# buttons.net
KiCad netlist of a schematic drawn in EAGLE
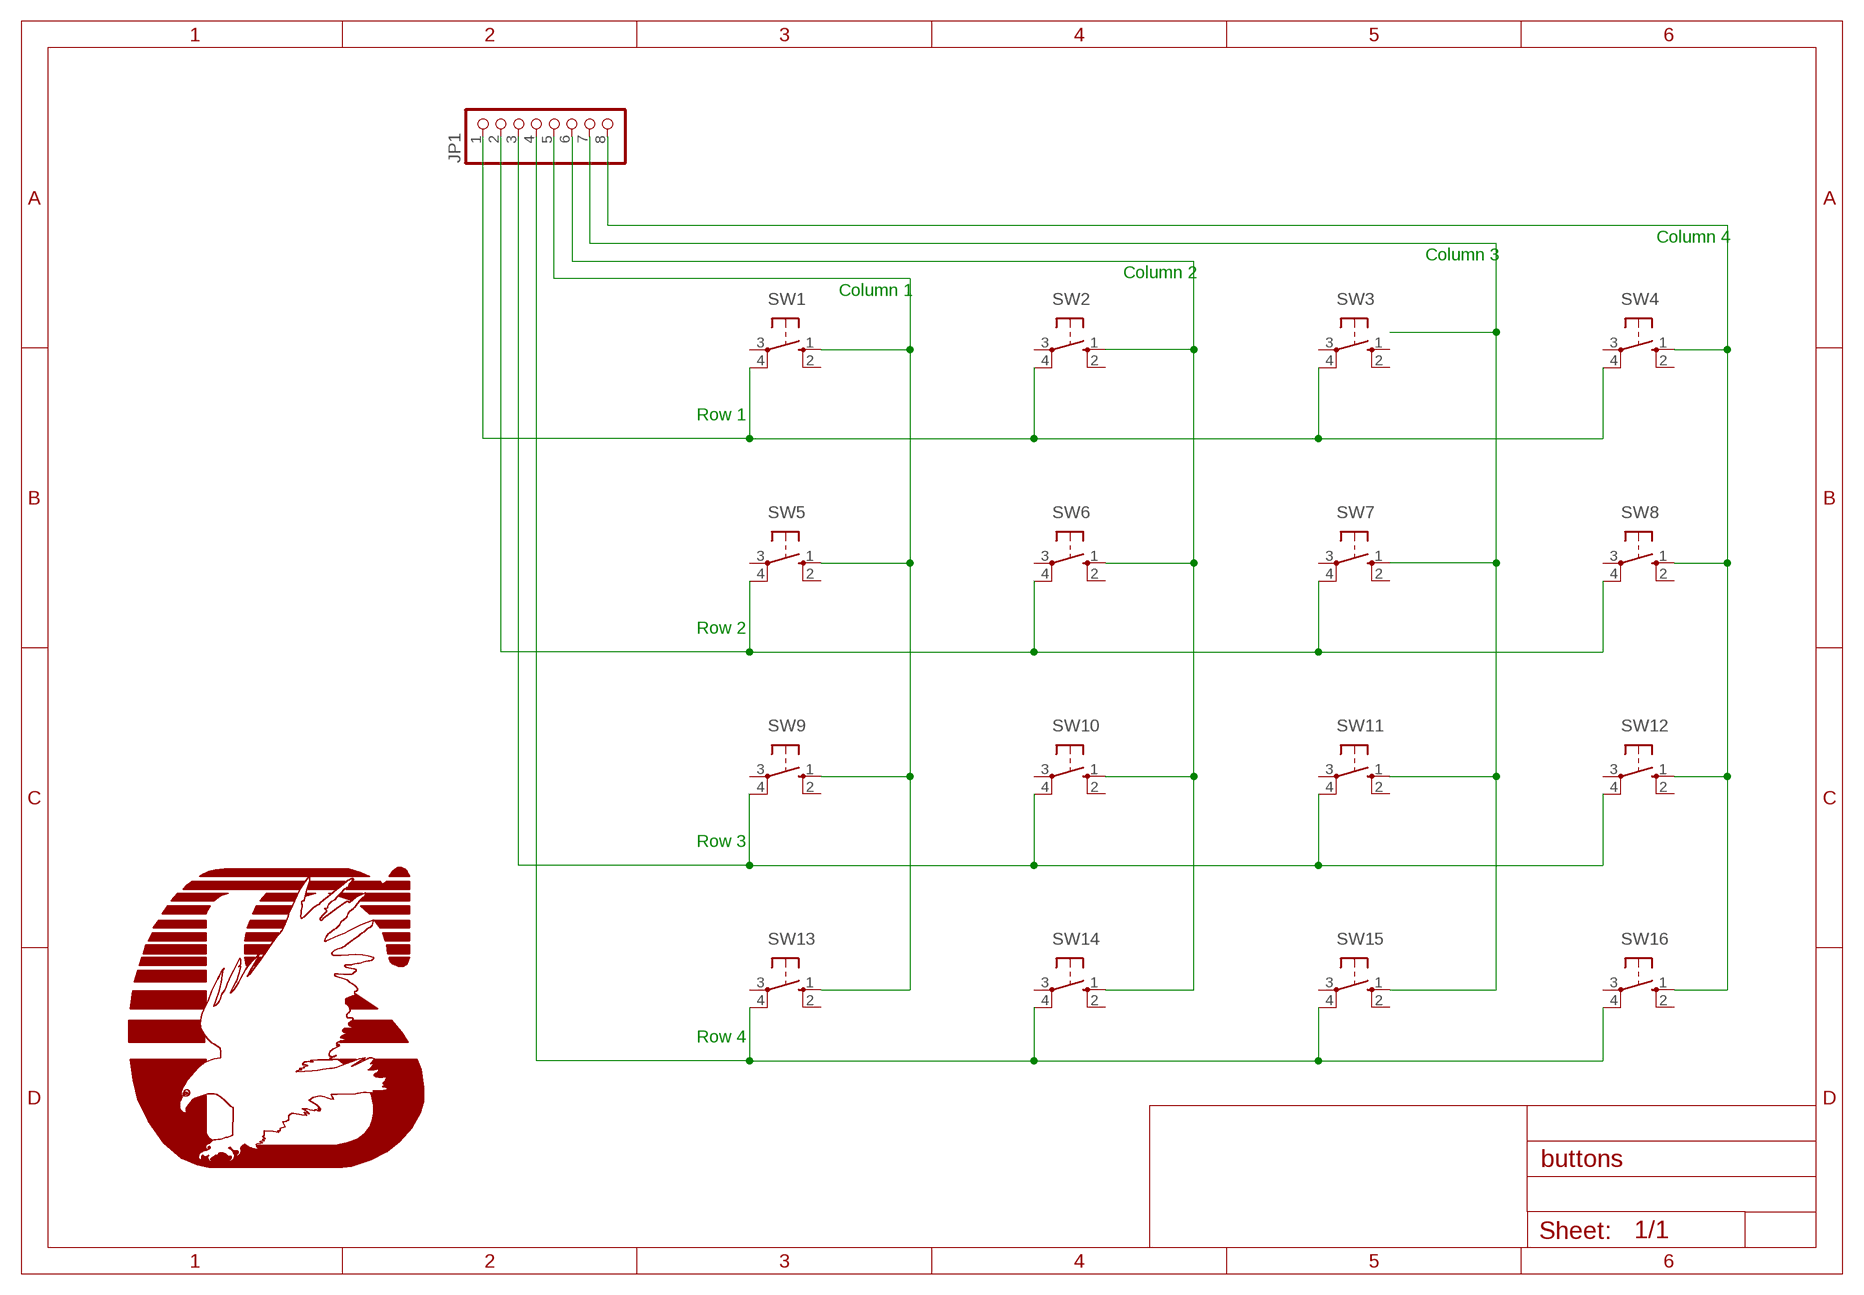
[diagram p0: schematic, sheet 1]

(export (version "E")
  (design (tool "Eeschema 10.0.6"))
  (components
    (comp (ref "JP1")
      (value "PINHD-1X8-3.5MM")
      (footprint "eagle-import:1X08-3.5MM")
      (libsource (lib "eagle-import") (part "PINHD-1X8-3.5MM"))
    )
    (comp (ref "SW1")
      (value "10-XX")
      (footprint "eagle-import:B3F-10XX")
      (libsource (lib "eagle-import") (part "10-XX"))
    )
    (comp (ref "SW2")
      (value "10-XX")
      (footprint "eagle-import:B3F-10XX")
      (libsource (lib "eagle-import") (part "10-XX"))
    )
    (comp (ref "SW3")
      (value "10-XX")
      (footprint "eagle-import:B3F-10XX")
      (libsource (lib "eagle-import") (part "10-XX"))
    )
    (comp (ref "SW4")
      (value "10-XX")
      (footprint "eagle-import:B3F-10XX")
      (libsource (lib "eagle-import") (part "10-XX"))
    )
    (comp (ref "SW5")
      (value "10-XX")
      (footprint "eagle-import:B3F-10XX")
      (libsource (lib "eagle-import") (part "10-XX"))
    )
    (comp (ref "SW6")
      (value "10-XX")
      (footprint "eagle-import:B3F-10XX")
      (libsource (lib "eagle-import") (part "10-XX"))
    )
    (comp (ref "SW7")
      (value "10-XX")
      (footprint "eagle-import:B3F-10XX")
      (libsource (lib "eagle-import") (part "10-XX"))
    )
    (comp (ref "SW8")
      (value "10-XX")
      (footprint "eagle-import:B3F-10XX")
      (libsource (lib "eagle-import") (part "10-XX"))
    )
    (comp (ref "SW9")
      (value "10-XX")
      (footprint "eagle-import:B3F-10XX")
      (libsource (lib "eagle-import") (part "10-XX"))
    )
    (comp (ref "SW10")
      (value "10-XX")
      (footprint "eagle-import:B3F-10XX")
      (libsource (lib "eagle-import") (part "10-XX"))
    )
    (comp (ref "SW11")
      (value "10-XX")
      (footprint "eagle-import:B3F-10XX")
      (libsource (lib "eagle-import") (part "10-XX"))
    )
    (comp (ref "SW12")
      (value "10-XX")
      (footprint "eagle-import:B3F-10XX")
      (libsource (lib "eagle-import") (part "10-XX"))
    )
    (comp (ref "SW13")
      (value "10-XX")
      (footprint "eagle-import:B3F-10XX")
      (libsource (lib "eagle-import") (part "10-XX"))
    )
    (comp (ref "SW14")
      (value "10-XX")
      (footprint "eagle-import:B3F-10XX")
      (libsource (lib "eagle-import") (part "10-XX"))
    )
    (comp (ref "SW15")
      (value "10-XX")
      (footprint "eagle-import:B3F-10XX")
      (libsource (lib "eagle-import") (part "10-XX"))
    )
    (comp (ref "SW16")
      (value "10-XX")
      (footprint "eagle-import:B3F-10XX")
      (libsource (lib "eagle-import") (part "10-XX"))
    )
  )
  (nets
    (net (code "1") (name "Net-(SW1-P1)") (class "Default")
      (node (ref "JP1") (pin "1") (pinfunction "1_1") (pintype "passive"))
      (node (ref "SW1") (pin "4") (pinfunction "P1_4") (pintype "passive"))
      (node (ref "SW2") (pin "4") (pinfunction "P1_4") (pintype "passive"))
      (node (ref "SW3") (pin "4") (pinfunction "P1_4") (pintype "passive"))
      (node (ref "SW4") (pin "4") (pinfunction "P1_4") (pintype "passive"))
    )
    (net (code "2") (name "Net-(SW1-S)") (class "Default")
      (node (ref "JP1") (pin "5") (pinfunction "5_5") (pintype "passive"))
      (node (ref "SW1") (pin "1") (pinfunction "S_1") (pintype "passive"))
      (node (ref "SW13") (pin "1") (pinfunction "S_1") (pintype "passive"))
      (node (ref "SW5") (pin "1") (pinfunction "S_1") (pintype "passive"))
      (node (ref "SW9") (pin "1") (pinfunction "S_1") (pintype "passive"))
    )
    (net (code "3") (name "Net-(SW5-P1)") (class "Default")
      (node (ref "JP1") (pin "2") (pinfunction "2_2") (pintype "passive"))
      (node (ref "SW5") (pin "4") (pinfunction "P1_4") (pintype "passive"))
      (node (ref "SW6") (pin "4") (pinfunction "P1_4") (pintype "passive"))
      (node (ref "SW7") (pin "4") (pinfunction "P1_4") (pintype "passive"))
      (node (ref "SW8") (pin "4") (pinfunction "P1_4") (pintype "passive"))
    )
    (net (code "4") (name "Net-(SW10-P1)") (class "Default")
      (node (ref "JP1") (pin "3") (pinfunction "3_3") (pintype "passive"))
      (node (ref "SW10") (pin "4") (pinfunction "P1_4") (pintype "passive"))
      (node (ref "SW11") (pin "4") (pinfunction "P1_4") (pintype "passive"))
      (node (ref "SW12") (pin "4") (pinfunction "P1_4") (pintype "passive"))
      (node (ref "SW9") (pin "4") (pinfunction "P1_4") (pintype "passive"))
    )
    (net (code "5") (name "Net-(SW10-S)") (class "Default")
      (node (ref "JP1") (pin "6") (pinfunction "6_6") (pintype "passive"))
      (node (ref "SW10") (pin "1") (pinfunction "S_1") (pintype "passive"))
      (node (ref "SW14") (pin "1") (pinfunction "S_1") (pintype "passive"))
      (node (ref "SW2") (pin "1") (pinfunction "S_1") (pintype "passive"))
      (node (ref "SW6") (pin "1") (pinfunction "S_1") (pintype "passive"))
    )
    (net (code "6") (name "Net-(SW11-S)") (class "Default")
      (node (ref "JP1") (pin "7") (pinfunction "7_7") (pintype "passive"))
      (node (ref "SW11") (pin "1") (pinfunction "S_1") (pintype "passive"))
      (node (ref "SW15") (pin "1") (pinfunction "S_1") (pintype "passive"))
      (node (ref "SW7") (pin "1") (pinfunction "S_1") (pintype "passive"))
    )
    (net (code "7") (name "Net-(SW12-S)") (class "Default")
      (node (ref "JP1") (pin "8") (pinfunction "8_8") (pintype "passive"))
      (node (ref "SW12") (pin "1") (pinfunction "S_1") (pintype "passive"))
      (node (ref "SW16") (pin "1") (pinfunction "S_1") (pintype "passive"))
      (node (ref "SW4") (pin "1") (pinfunction "S_1") (pintype "passive"))
      (node (ref "SW8") (pin "1") (pinfunction "S_1") (pintype "passive"))
    )
    (net (code "8") (name "Net-(SW13-P1)") (class "Default")
      (node (ref "JP1") (pin "4") (pinfunction "4_4") (pintype "passive"))
      (node (ref "SW13") (pin "4") (pinfunction "P1_4") (pintype "passive"))
      (node (ref "SW14") (pin "4") (pinfunction "P1_4") (pintype "passive"))
      (node (ref "SW15") (pin "4") (pinfunction "P1_4") (pintype "passive"))
      (node (ref "SW16") (pin "4") (pinfunction "P1_4") (pintype "passive"))
    )
    (net (code "9") (name "unconnected-(SW1-P-Pad3)") (class "Default")
      (node (ref "SW1") (pin "3") (pinfunction "P_3") (pintype "passive"))
    )
    (net (code "10") (name "unconnected-(SW1-S1-Pad2)") (class "Default")
      (node (ref "SW1") (pin "2") (pinfunction "S1_2") (pintype "passive"))
    )
    (net (code "11") (name "unconnected-(SW2-P-Pad3)") (class "Default")
      (node (ref "SW2") (pin "3") (pinfunction "P_3") (pintype "passive"))
    )
    (net (code "12") (name "unconnected-(SW2-S1-Pad2)") (class "Default")
      (node (ref "SW2") (pin "2") (pinfunction "S1_2") (pintype "passive"))
    )
    (net (code "13") (name "unconnected-(SW3-P-Pad3)") (class "Default")
      (node (ref "SW3") (pin "3") (pinfunction "P_3") (pintype "passive"))
    )
    (net (code "14") (name "unconnected-(SW3-S-Pad1)") (class "Default")
      (node (ref "SW3") (pin "1") (pinfunction "S_1") (pintype "passive"))
    )
    (net (code "15") (name "unconnected-(SW3-S1-Pad2)") (class "Default")
      (node (ref "SW3") (pin "2") (pinfunction "S1_2") (pintype "passive"))
    )
    (net (code "16") (name "unconnected-(SW4-P-Pad3)") (class "Default")
      (node (ref "SW4") (pin "3") (pinfunction "P_3") (pintype "passive"))
    )
    (net (code "17") (name "unconnected-(SW4-S1-Pad2)") (class "Default")
      (node (ref "SW4") (pin "2") (pinfunction "S1_2") (pintype "passive"))
    )
    (net (code "18") (name "unconnected-(SW5-P-Pad3)") (class "Default")
      (node (ref "SW5") (pin "3") (pinfunction "P_3") (pintype "passive"))
    )
    (net (code "19") (name "unconnected-(SW5-S1-Pad2)") (class "Default")
      (node (ref "SW5") (pin "2") (pinfunction "S1_2") (pintype "passive"))
    )
    (net (code "20") (name "unconnected-(SW6-P-Pad3)") (class "Default")
      (node (ref "SW6") (pin "3") (pinfunction "P_3") (pintype "passive"))
    )
    (net (code "21") (name "unconnected-(SW6-S1-Pad2)") (class "Default")
      (node (ref "SW6") (pin "2") (pinfunction "S1_2") (pintype "passive"))
    )
    (net (code "22") (name "unconnected-(SW7-P-Pad3)") (class "Default")
      (node (ref "SW7") (pin "3") (pinfunction "P_3") (pintype "passive"))
    )
    (net (code "23") (name "unconnected-(SW7-S1-Pad2)") (class "Default")
      (node (ref "SW7") (pin "2") (pinfunction "S1_2") (pintype "passive"))
    )
    (net (code "24") (name "unconnected-(SW8-P-Pad3)") (class "Default")
      (node (ref "SW8") (pin "3") (pinfunction "P_3") (pintype "passive"))
    )
    (net (code "25") (name "unconnected-(SW8-S1-Pad2)") (class "Default")
      (node (ref "SW8") (pin "2") (pinfunction "S1_2") (pintype "passive"))
    )
    (net (code "26") (name "unconnected-(SW9-P-Pad3)") (class "Default")
      (node (ref "SW9") (pin "3") (pinfunction "P_3") (pintype "passive"))
    )
    (net (code "27") (name "unconnected-(SW9-S1-Pad2)") (class "Default")
      (node (ref "SW9") (pin "2") (pinfunction "S1_2") (pintype "passive"))
    )
    (net (code "28") (name "unconnected-(SW10-P-Pad3)") (class "Default")
      (node (ref "SW10") (pin "3") (pinfunction "P_3") (pintype "passive"))
    )
    (net (code "29") (name "unconnected-(SW10-S1-Pad2)") (class "Default")
      (node (ref "SW10") (pin "2") (pinfunction "S1_2") (pintype "passive"))
    )
    (net (code "30") (name "unconnected-(SW11-P-Pad3)") (class "Default")
      (node (ref "SW11") (pin "3") (pinfunction "P_3") (pintype "passive"))
    )
    (net (code "31") (name "unconnected-(SW11-S1-Pad2)") (class "Default")
      (node (ref "SW11") (pin "2") (pinfunction "S1_2") (pintype "passive"))
    )
    (net (code "32") (name "unconnected-(SW12-P-Pad3)") (class "Default")
      (node (ref "SW12") (pin "3") (pinfunction "P_3") (pintype "passive"))
    )
    (net (code "33") (name "unconnected-(SW12-S1-Pad2)") (class "Default")
      (node (ref "SW12") (pin "2") (pinfunction "S1_2") (pintype "passive"))
    )
    (net (code "34") (name "unconnected-(SW13-P-Pad3)") (class "Default")
      (node (ref "SW13") (pin "3") (pinfunction "P_3") (pintype "passive"))
    )
    (net (code "35") (name "unconnected-(SW13-S1-Pad2)") (class "Default")
      (node (ref "SW13") (pin "2") (pinfunction "S1_2") (pintype "passive"))
    )
    (net (code "36") (name "unconnected-(SW14-P-Pad3)") (class "Default")
      (node (ref "SW14") (pin "3") (pinfunction "P_3") (pintype "passive"))
    )
    (net (code "37") (name "unconnected-(SW14-S1-Pad2)") (class "Default")
      (node (ref "SW14") (pin "2") (pinfunction "S1_2") (pintype "passive"))
    )
    (net (code "38") (name "unconnected-(SW15-P-Pad3)") (class "Default")
      (node (ref "SW15") (pin "3") (pinfunction "P_3") (pintype "passive"))
    )
    (net (code "39") (name "unconnected-(SW15-S1-Pad2)") (class "Default")
      (node (ref "SW15") (pin "2") (pinfunction "S1_2") (pintype "passive"))
    )
    (net (code "40") (name "unconnected-(SW16-P-Pad3)") (class "Default")
      (node (ref "SW16") (pin "3") (pinfunction "P_3") (pintype "passive"))
    )
    (net (code "41") (name "unconnected-(SW16-S1-Pad2)") (class "Default")
      (node (ref "SW16") (pin "2") (pinfunction "S1_2") (pintype "passive"))
    )
  )
)
